# 555timer.net
KiCad netlist of a schematic drawn in Altium Designer
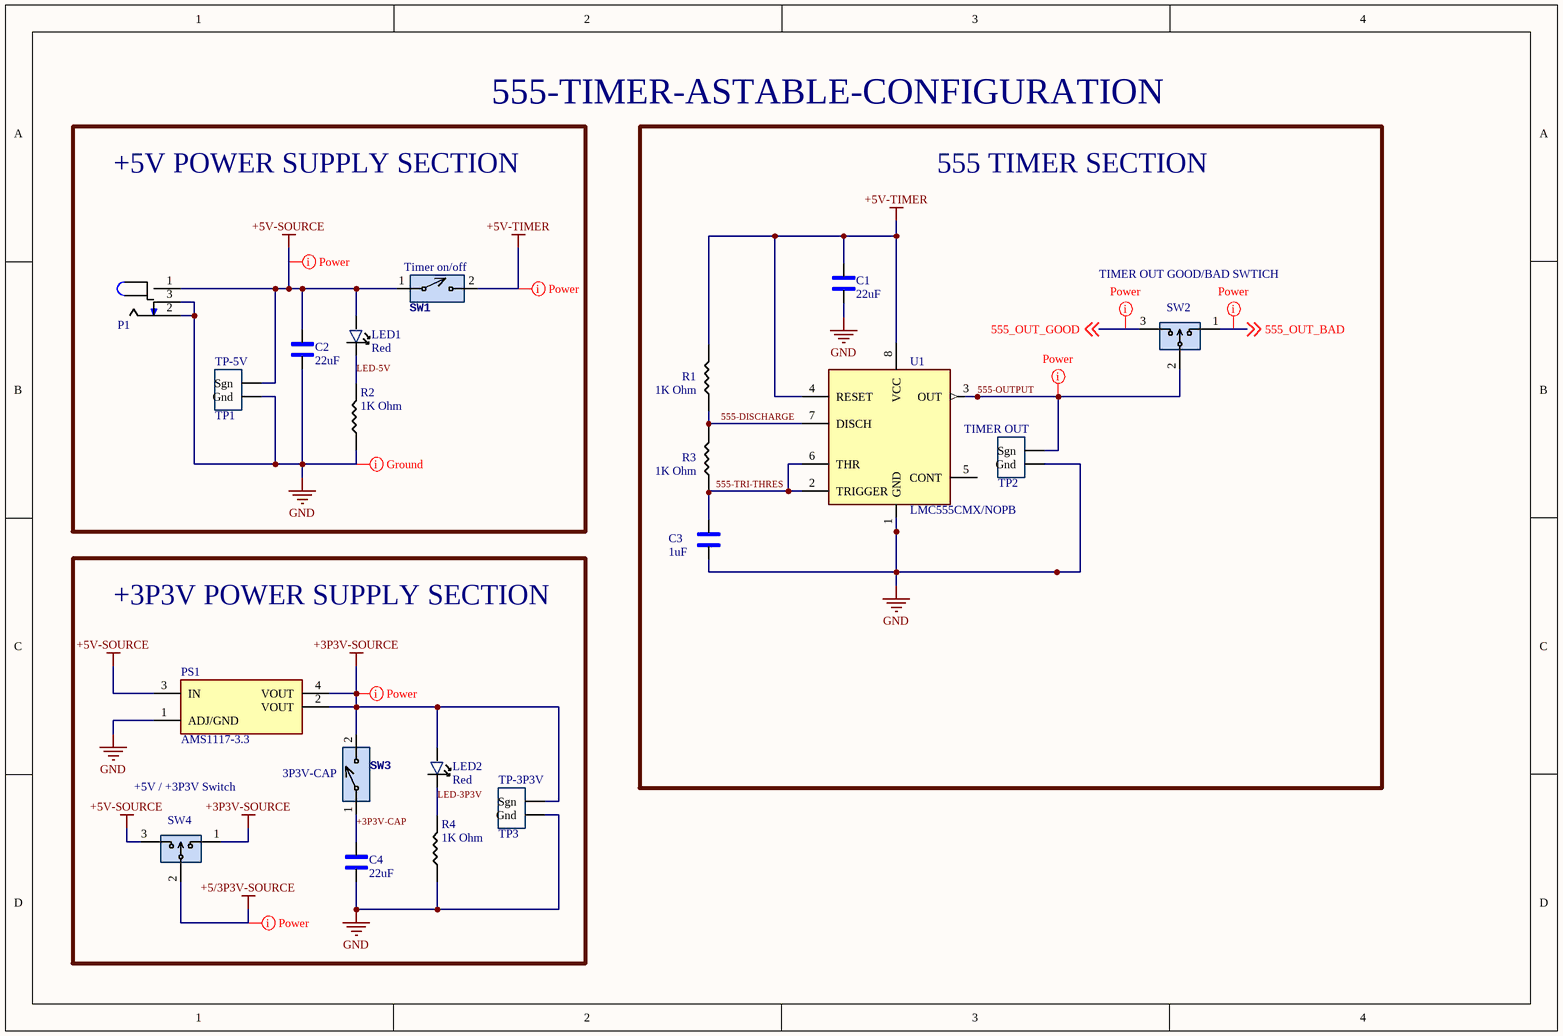
[diagram p0: 555timer.SchDoc]

(export (version "E")
  (design (tool "Eeschema 10.0.6"))
  (components
    (comp (ref "C1")
      (value "22uF")
      (footprint "1206_Passive_Capacitor")
      (description "22uF ±10% 25V X5R 1206 Multilayer Ceramic Capacitors MLCC - SMD/SMT RoHS")
      (fields (field (name "MFR PART #") "CL31A226KAHNNNE") (field (name "LCSC PART#") "C12891"))
      (libsource (lib "ECEN5730Lib_2023_05_DS (1)") (part "C_22uF_1206"))
    )
    (comp (ref "C2")
      (value "22uF")
      (footprint "1206_Passive_Capacitor")
      (description "22uF ±10% 25V X5R 1206 Multilayer Ceramic Capacitors MLCC - SMD/SMT RoHS")
      (fields (field (name "MFR PART #") "CL31A226KAHNNNE") (field (name "LCSC PART#") "C12891"))
      (libsource (lib "ECEN5730Lib_2023_05_DS (1)") (part "C_22uF_1206"))
    )
    (comp (ref "C3")
      (value "1uF")
      (footprint "1206_Passive_Capacitor")
      (description "MULTILAYER CERAMIC CAPACITORS MLCC - SMD/SMT 1UF 50V 1206 ROHS")
      (fields (field (name "MFR PART #") "CL31B105KBHNNNE") (field (name "LCSC PART#") "C1848"))
      (libsource (lib "ECEN5730Lib_2023_05_DS (1)") (part "C_1uF_1206"))
    )
    (comp (ref "C4")
      (value "22uF")
      (footprint "1206_Passive_Capacitor")
      (description "22uF ±10% 25V X5R 1206 Multilayer Ceramic Capacitors MLCC - SMD/SMT RoHS")
      (fields (field (name "MFR PART #") "CL31A226KAHNNNE") (field (name "LCSC PART#") "C12891"))
      (libsource (lib "ECEN5730Lib_2023_05_DS (1)") (part "C_22uF_1206"))
    )
    (comp (ref "LED1")
      (value "Red")
      (footprint "LED_1206")
      (description "Red 621~631nm 1206 Light Emitting Diodes (LED) RoHS")
      (fields (field (name "MFR PART #") "15-21/R6C-FQ1R1B/2T") (field (name "LCSC PART#") "C93133"))
      (libsource (lib "ECEN5730Lib_2023_05_DS (1)") (part "LED_RED_1206"))
    )
    (comp (ref "LED2")
      (value "Red")
      (footprint "LED_1206")
      (description "Red 621~631nm 1206 Light Emitting Diodes (LED) RoHS")
      (fields (field (name "MFR PART #") "15-21/R6C-FQ1R1B/2T") (field (name "LCSC PART#") "C93133"))
      (libsource (lib "ECEN5730Lib_2023_05_DS (1)") (part "LED_RED_1206"))
    )
    (comp (ref "P1")
      (value "Power Jack")
      (footprint "Power_Jack")
      (description "Power Barrel Connector Jack 2.10mm ID (0.083\"), 5.50mm OD (0.217\") Through Hole, Right Angle")
      (fields (field (name "MFR PART #") "PJ-102A") (field (name "LCSC PART#") "C136744"))
      (libsource (lib "ECEN5730Lib_2023_05_DS (1)") (part "P_Power Jack"))
    )
    (comp (ref "PS1")
      (value "AMS1117-3.3")
      (footprint "LDO")
      (description "LOW DROPOUT REGULATORS(LDO) POSITIVE FIXED 1.3V @ 800MA 15V 3.3V 1A SOT-223 ROHS")
      (fields (field (name "LCSC PART#") "C6186"))
      (libsource (lib "ECEN5730Lib_2023_05_DS (1)") (part "PS_AMS_LDO_3v3"))
    )
    (comp (ref "R1")
      (value "1K Ohm")
      (footprint "1206_Passive_Resitor")
      (description "CHIP RESISTOR - SURFACE MOUNT 1KOHMS ±1% 1/4W 1206 ROHS")
      (fields (field (name "MFR PART #") "RNCP1206FTD1K00CT") (field (name "LCSC PART#") "C4410"))
      (libsource (lib "ECEN5730Lib_2023_05_DS (1)") (part "R_1K_1206"))
    )
    (comp (ref "R2")
      (value "1K Ohm")
      (footprint "1206_Passive_Resitor")
      (description "CHIP RESISTOR - SURFACE MOUNT 1KOHMS ±1% 1/4W 1206 ROHS")
      (fields (field (name "MFR PART #") "RNCP1206FTD1K00CT") (field (name "LCSC PART#") "C4410"))
      (libsource (lib "ECEN5730Lib_2023_05_DS (1)") (part "R_1K_1206"))
    )
    (comp (ref "R3")
      (value "1K Ohm")
      (footprint "1206_Passive_Resitor")
      (description "CHIP RESISTOR - SURFACE MOUNT 1KOHMS ±1% 1/4W 1206 ROHS")
      (fields (field (name "MFR PART #") "RNCP1206FTD1K00CT") (field (name "LCSC PART#") "C4410"))
      (libsource (lib "ECEN5730Lib_2023_05_DS (1)") (part "R_1K_1206"))
    )
    (comp (ref "R4")
      (value "1K Ohm")
      (footprint "1206_Passive_Resitor")
      (description "CHIP RESISTOR - SURFACE MOUNT 1KOHMS ±1% 1/4W 1206 ROHS")
      (fields (field (name "MFR PART #") "RNCP1206FTD1K00CT") (field (name "LCSC PART#") "C4410"))
      (libsource (lib "ECEN5730Lib_2023_05_DS (1)") (part "R_1K_1206"))
    )
    (comp (ref "SW1")
      (value "SW_2Pin_100mil_Switch")
      (footprint "2Pin-Header-Conn")
      (description "2Pin Header")
      (fields (field (name "LCSC PART#") "C124375"))
      (libsource (lib "ECEN5730Lib_2023_05_DS (1)") (part "SW_2Pin_100mil_Switch"))
    )
    (comp (ref "SW2")
      (value "PREC003SAAN-RC")
      (footprint "3_PIN_100mil")
      (description "Connector Header Through Hole 3 position 0.100\" (2.54mm)")
      (fields (field (name "LCSC PART#") "C49257"))
      (libsource (lib "ECEN5730Lib_2023_05_DS (1)") (part "SW_3Pin_100mil_Switch"))
    )
    (comp (ref "SW3")
      (value "SW_2Pin_100mil_Switch")
      (footprint "2Pin-Header-Conn")
      (description "2Pin Header")
      (fields (field (name "LCSC PART#") "C124375"))
      (libsource (lib "") (part "SW_2Pin_100mil_Switch_1"))
    )
    (comp (ref "SW4")
      (value "PREC003SAAN-RC")
      (footprint "3_PIN_100mil")
      (description "Connector Header Through Hole 3 position 0.100\" (2.54mm)")
      (fields (field (name "LCSC PART#") "C49257"))
      (libsource (lib "ECEN5730Lib_2023_05_DS (1)") (part "SW_3Pin_100mil_Switch"))
    )
    (comp (ref "TP1")
      (value "TP-5V")
      (footprint "TP10x_Probe")
      (description "Test Point 300 mil centers")
      (libsource (lib "ECEN5730Lib_2023_05_DS (1)") (part "TP_10x_Probe"))
    )
    (comp (ref "TP2")
      (value "TIMER OUT")
      (footprint "TP10x_Probe")
      (description "Test Point 300 mil centers")
      (libsource (lib "ECEN5730Lib_2023_05_DS (1)") (part "TP_10x_Probe"))
    )
    (comp (ref "TP3")
      (value "TP-3P3V")
      (footprint "TP10x_Probe")
      (description "Test Point 300 mil centers")
      (libsource (lib "ECEN5730Lib_2023_05_DS (1)") (part "TP_10x_Probe"))
    )
    (comp (ref "U1")
      (value "LMC555CMX/NOPB")
      (footprint "TS555IDTTR")
      (description "555 Type, Timer/Oscillator _Single_ IC 3MHz 8-SO")
      (fields (field (name "LCSC PART#") "C90760"))
      (libsource (lib "ECEN5730Lib_2023_05_DS (1)") (part "U_555_Fast"))
    )
  )
  (nets
    (net (code "1") (name "+3P3V-SOURCE") (class "Default")
      (node (ref "LED2") (pin "1") (pinfunction "1_1") (pintype "passive"))
      (node (ref "PS1") (pin "2") (pinfunction "VOUT_2") (pintype "power_in"))
      (node (ref "PS1") (pin "4") (pinfunction "VOUT_4") (pintype "power_in"))
      (node (ref "SW3") (pin "2") (pinfunction "2_2") (pintype "passive"))
      (node (ref "SW4") (pin "1") (pinfunction "1_1") (pintype "passive"))
      (node (ref "TP3") (pin "1") (pinfunction "Sgn_1") (pintype "passive"))
    )
    (net (code "2") (name "+5V-SOURCE") (class "Default")
      (node (ref "C2") (pin "2") (pinfunction "2_2") (pintype "passive"))
      (node (ref "LED1") (pin "1") (pinfunction "1_1") (pintype "passive"))
      (node (ref "P1") (pin "1") (pinfunction "1_1") (pintype "power_in"))
      (node (ref "PS1") (pin "3") (pinfunction "IN_3") (pintype "power_in"))
      (node (ref "SW1") (pin "1") (pinfunction "1_1") (pintype "passive"))
      (node (ref "SW4") (pin "3") (pinfunction "3_3") (pintype "passive"))
      (node (ref "TP1") (pin "1") (pinfunction "Sgn_1") (pintype "passive"))
    )
    (net (code "3") (name "+5V-TIMER") (class "Default")
      (node (ref "C1") (pin "2") (pinfunction "2_2") (pintype "passive"))
      (node (ref "R1") (pin "2") (pinfunction "2_2") (pintype "passive"))
      (node (ref "SW1") (pin "2") (pinfunction "2_2") (pintype "passive"))
      (node (ref "U1") (pin "4") (pinfunction "RESET_4") (pintype "passive"))
      (node (ref "U1") (pin "8") (pinfunction "VCC_8") (pintype "power_in"))
    )
    (net (code "4") (name "+5{slash}3P3V-SOURCE") (class "Default")
      (node (ref "SW4") (pin "2") (pinfunction "2_2") (pintype "passive"))
    )
    (net (code "5") (name "/+3P3V-CAP") (class "Default")
      (node (ref "C4") (pin "2") (pinfunction "2_2") (pintype "passive"))
      (node (ref "SW3") (pin "1") (pinfunction "1_1") (pintype "passive"))
    )
    (net (code "6") (name "/555-DISCHARGE") (class "Default")
      (node (ref "R1") (pin "1") (pinfunction "1_1") (pintype "passive"))
      (node (ref "R3") (pin "2") (pinfunction "2_2") (pintype "passive"))
      (node (ref "U1") (pin "7") (pinfunction "DISCH_7") (pintype "passive"))
    )
    (net (code "7") (name "/555-OUTPUT") (class "Default")
      (node (ref "SW2") (pin "2") (pinfunction "2_2") (pintype "passive"))
      (node (ref "TP2") (pin "1") (pinfunction "Sgn_1") (pintype "passive"))
      (node (ref "U1") (pin "3") (pinfunction "OUT_3") (pintype "output"))
    )
    (net (code "8") (name "/555-TRI-THRES") (class "Default")
      (node (ref "C3") (pin "2") (pinfunction "2_2") (pintype "passive"))
      (node (ref "R3") (pin "1") (pinfunction "1_1") (pintype "passive"))
      (node (ref "U1") (pin "2") (pinfunction "TRIGGER_2") (pintype "passive"))
      (node (ref "U1") (pin "6") (pinfunction "THR_6") (pintype "passive"))
    )
    (net (code "9") (name "/LED-3P3V") (class "Default")
      (node (ref "LED2") (pin "2") (pinfunction "2_2") (pintype "passive"))
      (node (ref "R4") (pin "2") (pinfunction "2_2") (pintype "passive"))
    )
    (net (code "10") (name "/LED-5V") (class "Default")
      (node (ref "LED1") (pin "2") (pinfunction "2_2") (pintype "passive"))
      (node (ref "R2") (pin "2") (pinfunction "2_2") (pintype "passive"))
    )
    (net (code "11") (name "555_OUT_BAD") (class "Default")
      (node (ref "SW2") (pin "1") (pinfunction "1_1") (pintype "passive"))
    )
    (net (code "12") (name "555_OUT_GOOD") (class "Default")
      (node (ref "SW2") (pin "3") (pinfunction "3_3") (pintype "passive"))
    )
    (net (code "13") (name "GND") (class "Default")
      (node (ref "C1") (pin "1") (pinfunction "1_1") (pintype "passive"))
      (node (ref "C2") (pin "1") (pinfunction "1_1") (pintype "passive"))
      (node (ref "C3") (pin "1") (pinfunction "1_1") (pintype "passive"))
      (node (ref "C4") (pin "1") (pinfunction "1_1") (pintype "passive"))
      (node (ref "P1") (pin "2") (pinfunction "2_2") (pintype "power_in"))
      (node (ref "P1") (pin "3") (pinfunction "3_3") (pintype "power_in"))
      (node (ref "PS1") (pin "1") (pinfunction "ADJ/GND_1") (pintype "passive"))
      (node (ref "R2") (pin "1") (pinfunction "1_1") (pintype "passive"))
      (node (ref "R4") (pin "1") (pinfunction "1_1") (pintype "passive"))
      (node (ref "TP1") (pin "2") (pinfunction "Gnd_2") (pintype "passive"))
      (node (ref "TP2") (pin "2") (pinfunction "Gnd_2") (pintype "passive"))
      (node (ref "TP3") (pin "2") (pinfunction "Gnd_2") (pintype "passive"))
      (node (ref "U1") (pin "1") (pinfunction "GND_1") (pintype "power_in"))
    )
    (net (code "14") (name "unconnected-(U1-CONT-Pad5)") (class "Default")
      (node (ref "U1") (pin "5") (pinfunction "CONT_5") (pintype "passive"))
    )
  )
)
